# main.net
KiCad netlist of a schematic drawn in Altium Designer
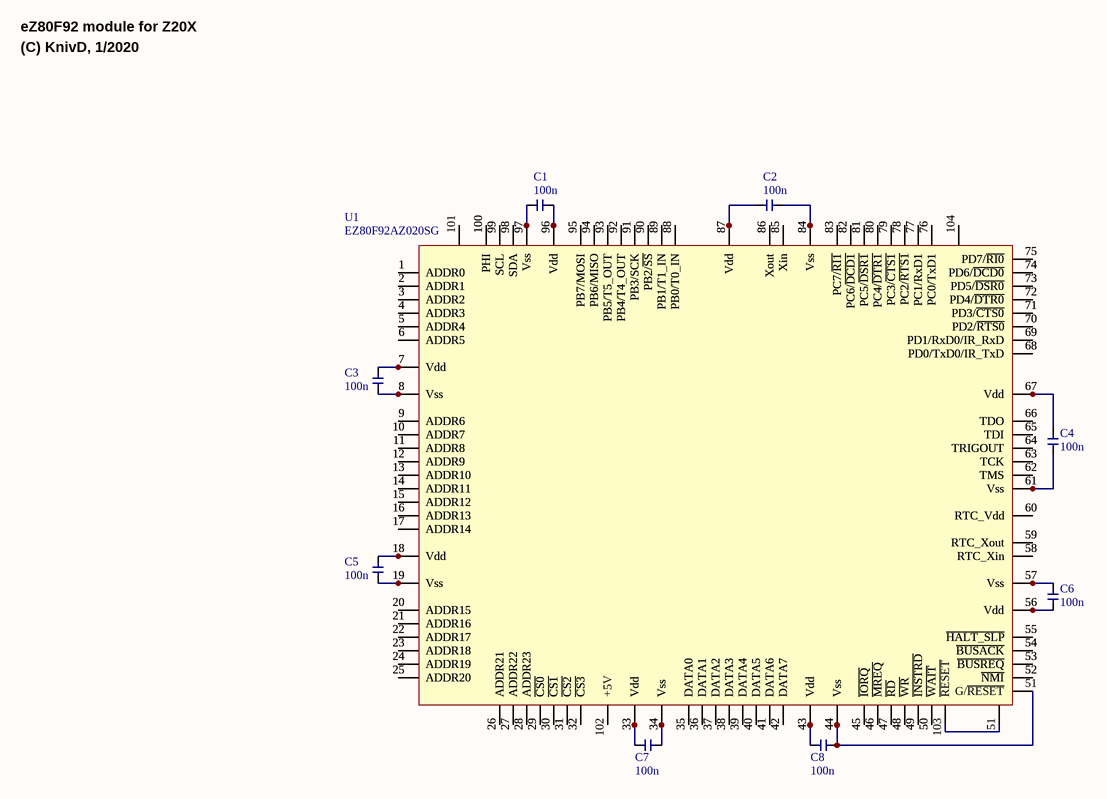
[diagram p0: main.SchDoc]

(export (version "E")
  (design (tool "Eeschema 10.0.6"))
  (components
    (comp (ref "C1")
      (value "100n")
      (footprint "_0805_CAP")
      (description "Capacitor")
      (libsource (lib "Discretes") (part "Capacitor"))
    )
    (comp (ref "C2")
      (value "100n")
      (footprint "_0805_CAP")
      (description "Capacitor")
      (libsource (lib "Discretes") (part "Capacitor"))
    )
    (comp (ref "C3")
      (value "100n")
      (footprint "_0805_CAP")
      (description "Capacitor")
      (libsource (lib "Discretes") (part "Capacitor"))
    )
    (comp (ref "C4")
      (value "100n")
      (footprint "_0805_CAP")
      (description "Capacitor")
      (libsource (lib "Discretes") (part "Capacitor"))
    )
    (comp (ref "C5")
      (value "100n")
      (footprint "_0805_CAP")
      (description "Capacitor")
      (libsource (lib "Discretes") (part "Capacitor"))
    )
    (comp (ref "C6")
      (value "100n")
      (footprint "_0805_CAP")
      (description "Capacitor")
      (libsource (lib "Discretes") (part "Capacitor"))
    )
    (comp (ref "C7")
      (value "100n")
      (footprint "_0805_CAP")
      (description "Capacitor")
      (libsource (lib "Discretes") (part "Capacitor"))
    )
    (comp (ref "C8")
      (value "100n")
      (footprint "_0805_CAP")
      (description "Capacitor")
      (libsource (lib "Discretes") (part "Capacitor"))
    )
    (comp (ref "MOD1")
      (value "Z20X CPU Module")
      (footprint "PGA100X15")
      (libsource (lib "Modules") (part "Z20X CPU Module"))
    )
    (comp (ref "U1")
      (value "EZ80F92AZ020SG")
      (footprint "QFP50P1600X1600X170-100N")
      (description "eZ80Acclaim!® Flash Microcontrollers")
      (fields (field (name "MANUFACTURER") "Zilog"))
      (libsource (lib "IC Microcontrollers and Processors") (part "eZ80F92/93"))
    )
  )
  (nets
    (net (code "1") (name "Net-(C1-Pad1)") (class "Default")
      (node (ref "C1") (pin "1") (pintype "passive"))
      (node (ref "MOD1") (pin "96") (pinfunction "Vdd_96") (pintype "passive"))
      (node (ref "U1") (pin "96") (pinfunction "Vdd_96") (pintype "passive"))
    )
    (net (code "2") (name "Net-(C1-Pad2)") (class "Default")
      (node (ref "C1") (pin "2") (pintype "passive"))
      (node (ref "MOD1") (pin "97") (pinfunction "Vss_97") (pintype "passive"))
      (node (ref "U1") (pin "97") (pinfunction "Vss_97") (pintype "passive"))
    )
    (net (code "3") (name "Net-(C2-Pad1)") (class "Default")
      (node (ref "C2") (pin "1") (pintype "passive"))
      (node (ref "MOD1") (pin "84") (pinfunction "Vss_84") (pintype "passive"))
      (node (ref "U1") (pin "84") (pinfunction "Vss_84") (pintype "passive"))
    )
    (net (code "4") (name "Net-(C2-Pad2)") (class "Default")
      (node (ref "C2") (pin "2") (pintype "passive"))
      (node (ref "MOD1") (pin "87") (pinfunction "Vdd_87") (pintype "passive"))
      (node (ref "U1") (pin "87") (pinfunction "Vdd_87") (pintype "passive"))
    )
    (net (code "5") (name "Net-(C3-Pad1)") (class "Default")
      (node (ref "C3") (pin "1") (pintype "passive"))
      (node (ref "MOD1") (pin "7") (pinfunction "Vdd_7") (pintype "passive"))
      (node (ref "U1") (pin "7") (pinfunction "Vdd_7") (pintype "passive"))
    )
    (net (code "6") (name "Net-(C3-Pad2)") (class "Default")
      (node (ref "C3") (pin "2") (pintype "passive"))
      (node (ref "MOD1") (pin "8") (pinfunction "Vss_8") (pintype "passive"))
      (node (ref "U1") (pin "8") (pinfunction "Vss_8") (pintype "passive"))
    )
    (net (code "7") (name "Net-(C4-Pad1)") (class "Default")
      (node (ref "C4") (pin "1") (pintype "passive"))
      (node (ref "MOD1") (pin "61") (pinfunction "Vss_61") (pintype "passive"))
      (node (ref "U1") (pin "61") (pinfunction "Vss_61") (pintype "passive"))
    )
    (net (code "8") (name "Net-(C4-Pad2)") (class "Default")
      (node (ref "C4") (pin "2") (pintype "passive"))
      (node (ref "MOD1") (pin "67") (pinfunction "Vdd_67") (pintype "passive"))
      (node (ref "U1") (pin "67") (pinfunction "Vdd_67") (pintype "passive"))
    )
    (net (code "9") (name "Net-(C5-Pad1)") (class "Default")
      (node (ref "C5") (pin "1") (pintype "passive"))
      (node (ref "MOD1") (pin "18") (pinfunction "Vdd_18") (pintype "passive"))
      (node (ref "U1") (pin "18") (pinfunction "Vdd_18") (pintype "passive"))
    )
    (net (code "10") (name "Net-(C5-Pad2)") (class "Default")
      (node (ref "C5") (pin "2") (pintype "passive"))
      (node (ref "MOD1") (pin "19") (pinfunction "Vss_19") (pintype "passive"))
      (node (ref "U1") (pin "19") (pinfunction "Vss_19") (pintype "passive"))
    )
    (net (code "11") (name "Net-(C6-Pad1)") (class "Default")
      (node (ref "C6") (pin "1") (pintype "passive"))
      (node (ref "MOD1") (pin "56") (pinfunction "Vdd_56") (pintype "passive"))
      (node (ref "U1") (pin "56") (pinfunction "Vdd_56") (pintype "passive"))
    )
    (net (code "12") (name "Net-(C6-Pad2)") (class "Default")
      (node (ref "C6") (pin "2") (pintype "passive"))
      (node (ref "MOD1") (pin "57") (pinfunction "Vss_57") (pintype "passive"))
      (node (ref "U1") (pin "57") (pinfunction "Vss_57") (pintype "passive"))
    )
    (net (code "13") (name "Net-(C7-Pad1)") (class "Default")
      (node (ref "C7") (pin "1") (pintype "passive"))
      (node (ref "MOD1") (pin "33") (pinfunction "Vdd_33") (pintype "passive"))
      (node (ref "U1") (pin "33") (pinfunction "Vdd_33") (pintype "passive"))
    )
    (net (code "14") (name "Net-(C7-Pad2)") (class "Default")
      (node (ref "C7") (pin "2") (pintype "passive"))
      (node (ref "MOD1") (pin "34") (pinfunction "Vss_34") (pintype "passive"))
      (node (ref "U1") (pin "34") (pinfunction "Vss_34") (pintype "passive"))
    )
    (net (code "15") (name "Net-(C8-Pad1)") (class "Default")
      (node (ref "C8") (pin "1") (pintype "passive"))
      (node (ref "MOD1") (pin "43") (pinfunction "Vdd_43") (pintype "passive"))
      (node (ref "U1") (pin "43") (pinfunction "Vdd_43") (pintype "passive"))
    )
    (net (code "16") (name "Net-(MOD1-ADDR0)") (class "Default")
      (node (ref "MOD1") (pin "1") (pinfunction "ADDR0_1") (pintype "passive"))
      (node (ref "U1") (pin "1") (pinfunction "ADDR0_1") (pintype "passive"))
    )
    (net (code "17") (name "Net-(MOD1-ADDR1)") (class "Default")
      (node (ref "MOD1") (pin "2") (pinfunction "ADDR1_2") (pintype "passive"))
      (node (ref "U1") (pin "2") (pinfunction "ADDR1_2") (pintype "passive"))
    )
    (net (code "18") (name "Net-(MOD1-ADDR2)") (class "Default")
      (node (ref "MOD1") (pin "3") (pinfunction "ADDR2_3") (pintype "passive"))
      (node (ref "U1") (pin "3") (pinfunction "ADDR2_3") (pintype "passive"))
    )
    (net (code "19") (name "Net-(MOD1-ADDR3)") (class "Default")
      (node (ref "MOD1") (pin "4") (pinfunction "ADDR3_4") (pintype "passive"))
      (node (ref "U1") (pin "4") (pinfunction "ADDR3_4") (pintype "passive"))
    )
    (net (code "20") (name "Net-(MOD1-ADDR4)") (class "Default")
      (node (ref "MOD1") (pin "5") (pinfunction "ADDR4_5") (pintype "passive"))
      (node (ref "U1") (pin "5") (pinfunction "ADDR4_5") (pintype "passive"))
    )
    (net (code "21") (name "Net-(MOD1-ADDR5)") (class "Default")
      (node (ref "MOD1") (pin "6") (pinfunction "ADDR5_6") (pintype "passive"))
      (node (ref "U1") (pin "6") (pinfunction "ADDR5_6") (pintype "passive"))
    )
    (net (code "22") (name "Net-(MOD1-ADDR6)") (class "Default")
      (node (ref "MOD1") (pin "9") (pinfunction "ADDR6_9") (pintype "passive"))
      (node (ref "U1") (pin "9") (pinfunction "ADDR6_9") (pintype "passive"))
    )
    (net (code "23") (name "Net-(MOD1-ADDR7)") (class "Default")
      (node (ref "MOD1") (pin "10") (pinfunction "ADDR7_10") (pintype "passive"))
      (node (ref "U1") (pin "10") (pinfunction "ADDR7_10") (pintype "passive"))
    )
    (net (code "24") (name "Net-(MOD1-ADDR8)") (class "Default")
      (node (ref "MOD1") (pin "11") (pinfunction "ADDR8_11") (pintype "passive"))
      (node (ref "U1") (pin "11") (pinfunction "ADDR8_11") (pintype "passive"))
    )
    (net (code "25") (name "Net-(MOD1-ADDR9)") (class "Default")
      (node (ref "MOD1") (pin "12") (pinfunction "ADDR9_12") (pintype "passive"))
      (node (ref "U1") (pin "12") (pinfunction "ADDR9_12") (pintype "passive"))
    )
    (net (code "26") (name "Net-(MOD1-ADDR10)") (class "Default")
      (node (ref "MOD1") (pin "13") (pinfunction "ADDR10_13") (pintype "passive"))
      (node (ref "U1") (pin "13") (pinfunction "ADDR10_13") (pintype "passive"))
    )
    (net (code "27") (name "Net-(MOD1-ADDR11)") (class "Default")
      (node (ref "MOD1") (pin "14") (pinfunction "ADDR11_14") (pintype "passive"))
      (node (ref "U1") (pin "14") (pinfunction "ADDR11_14") (pintype "passive"))
    )
    (net (code "28") (name "Net-(MOD1-ADDR12)") (class "Default")
      (node (ref "MOD1") (pin "15") (pinfunction "ADDR12_15") (pintype "passive"))
      (node (ref "U1") (pin "15") (pinfunction "ADDR12_15") (pintype "passive"))
    )
    (net (code "29") (name "Net-(MOD1-ADDR13)") (class "Default")
      (node (ref "MOD1") (pin "16") (pinfunction "ADDR13_16") (pintype "passive"))
      (node (ref "U1") (pin "16") (pinfunction "ADDR13_16") (pintype "passive"))
    )
    (net (code "30") (name "Net-(MOD1-ADDR14)") (class "Default")
      (node (ref "MOD1") (pin "17") (pinfunction "ADDR14_17") (pintype "passive"))
      (node (ref "U1") (pin "17") (pinfunction "ADDR14_17") (pintype "passive"))
    )
    (net (code "31") (name "Net-(MOD1-ADDR15)") (class "Default")
      (node (ref "MOD1") (pin "20") (pinfunction "ADDR15_20") (pintype "passive"))
      (node (ref "U1") (pin "20") (pinfunction "ADDR15_20") (pintype "passive"))
    )
    (net (code "32") (name "Net-(MOD1-ADDR16)") (class "Default")
      (node (ref "MOD1") (pin "21") (pinfunction "ADDR16_21") (pintype "passive"))
      (node (ref "U1") (pin "21") (pinfunction "ADDR16_21") (pintype "passive"))
    )
    (net (code "33") (name "Net-(MOD1-ADDR17)") (class "Default")
      (node (ref "MOD1") (pin "22") (pinfunction "ADDR17_22") (pintype "passive"))
      (node (ref "U1") (pin "22") (pinfunction "ADDR17_22") (pintype "passive"))
    )
    (net (code "34") (name "Net-(MOD1-ADDR18)") (class "Default")
      (node (ref "MOD1") (pin "23") (pinfunction "ADDR18_23") (pintype "passive"))
      (node (ref "U1") (pin "23") (pinfunction "ADDR18_23") (pintype "passive"))
    )
    (net (code "35") (name "Net-(MOD1-ADDR19)") (class "Default")
      (node (ref "MOD1") (pin "24") (pinfunction "ADDR19_24") (pintype "passive"))
      (node (ref "U1") (pin "24") (pinfunction "ADDR19_24") (pintype "passive"))
    )
    (net (code "36") (name "Net-(MOD1-ADDR20)") (class "Default")
      (node (ref "MOD1") (pin "25") (pinfunction "ADDR20_25") (pintype "passive"))
      (node (ref "U1") (pin "25") (pinfunction "ADDR20_25") (pintype "passive"))
    )
    (net (code "37") (name "Net-(MOD1-ADDR21)") (class "Default")
      (node (ref "MOD1") (pin "26") (pinfunction "ADDR21_26") (pintype "passive"))
      (node (ref "U1") (pin "26") (pinfunction "ADDR21_26") (pintype "passive"))
    )
    (net (code "38") (name "Net-(MOD1-ADDR22)") (class "Default")
      (node (ref "MOD1") (pin "27") (pinfunction "ADDR22_27") (pintype "passive"))
      (node (ref "U1") (pin "27") (pinfunction "ADDR22_27") (pintype "passive"))
    )
    (net (code "39") (name "Net-(MOD1-ADDR23)") (class "Default")
      (node (ref "MOD1") (pin "28") (pinfunction "ADDR23_28") (pintype "passive"))
      (node (ref "U1") (pin "28") (pinfunction "ADDR23_28") (pintype "passive"))
    )
    (net (code "40") (name "Net-(MOD1-DATA0)") (class "Default")
      (node (ref "MOD1") (pin "35") (pinfunction "DATA0_35") (pintype "passive"))
      (node (ref "U1") (pin "35") (pinfunction "DATA0_35") (pintype "passive"))
    )
    (net (code "41") (name "Net-(MOD1-DATA1)") (class "Default")
      (node (ref "MOD1") (pin "36") (pinfunction "DATA1_36") (pintype "passive"))
      (node (ref "U1") (pin "36") (pinfunction "DATA1_36") (pintype "passive"))
    )
    (net (code "42") (name "Net-(MOD1-DATA2)") (class "Default")
      (node (ref "MOD1") (pin "37") (pinfunction "DATA2_37") (pintype "passive"))
      (node (ref "U1") (pin "37") (pinfunction "DATA2_37") (pintype "passive"))
    )
    (net (code "43") (name "Net-(MOD1-DATA3)") (class "Default")
      (node (ref "MOD1") (pin "38") (pinfunction "DATA3_38") (pintype "passive"))
      (node (ref "U1") (pin "38") (pinfunction "DATA3_38") (pintype "passive"))
    )
    (net (code "44") (name "Net-(MOD1-DATA4)") (class "Default")
      (node (ref "MOD1") (pin "39") (pinfunction "DATA4_39") (pintype "passive"))
      (node (ref "U1") (pin "39") (pinfunction "DATA4_39") (pintype "passive"))
    )
    (net (code "45") (name "Net-(MOD1-DATA5)") (class "Default")
      (node (ref "MOD1") (pin "40") (pinfunction "DATA5_40") (pintype "passive"))
      (node (ref "U1") (pin "40") (pinfunction "DATA5_40") (pintype "passive"))
    )
    (net (code "46") (name "Net-(MOD1-DATA6)") (class "Default")
      (node (ref "MOD1") (pin "41") (pinfunction "DATA6_41") (pintype "passive"))
      (node (ref "U1") (pin "41") (pinfunction "DATA6_41") (pintype "passive"))
    )
    (net (code "47") (name "Net-(MOD1-DATA7)") (class "Default")
      (node (ref "MOD1") (pin "42") (pinfunction "DATA7_42") (pintype "passive"))
      (node (ref "U1") (pin "42") (pinfunction "DATA7_42") (pintype "passive"))
    )
    (net (code "48") (name "Net-(MOD1-G{slash}~{RESET})") (class "Default")
      (node (ref "C8") (pin "2") (pintype "passive"))
      (node (ref "MOD1") (pin "44") (pinfunction "Vss_44") (pintype "passive"))
      (node (ref "MOD1") (pin "51") (pinfunction "G/~{RESET}_51") (pintype "passive"))
      (node (ref "U1") (pin "44") (pinfunction "Vss_44") (pintype "passive"))
    )
    (net (code "49") (name "Net-(MOD1-PB0{slash}T0_IN)") (class "Default")
      (node (ref "MOD1") (pin "88") (pinfunction "PB0/T0_IN_88") (pintype "passive"))
      (node (ref "U1") (pin "88") (pinfunction "PB0/T0_IN_88") (pintype "passive"))
    )
    (net (code "50") (name "Net-(MOD1-PB1{slash}T1_IN)") (class "Default")
      (node (ref "MOD1") (pin "89") (pinfunction "PB1/T1_IN_89") (pintype "passive"))
      (node (ref "U1") (pin "89") (pinfunction "PB1/T1_IN_89") (pintype "passive"))
    )
    (net (code "51") (name "Net-(MOD1-PB2{slash}~{SS})") (class "Default")
      (node (ref "MOD1") (pin "90") (pinfunction "PB2/~{SS}_90") (pintype "passive"))
      (node (ref "U1") (pin "90") (pinfunction "PB2/~{SS}_90") (pintype "passive"))
    )
    (net (code "52") (name "Net-(MOD1-PB3{slash}SCK)") (class "Default")
      (node (ref "MOD1") (pin "91") (pinfunction "PB3/SCK_91") (pintype "passive"))
      (node (ref "U1") (pin "91") (pinfunction "PB3/SCK_91") (pintype "passive"))
    )
    (net (code "53") (name "Net-(MOD1-PB4{slash}T4_OUT)") (class "Default")
      (node (ref "MOD1") (pin "92") (pinfunction "PB4/T4_OUT_92") (pintype "passive"))
      (node (ref "U1") (pin "92") (pinfunction "PB4/T4_OUT_92") (pintype "passive"))
    )
    (net (code "54") (name "Net-(MOD1-PB5{slash}T5_OUT)") (class "Default")
      (node (ref "MOD1") (pin "93") (pinfunction "PB5/T5_OUT_93") (pintype "passive"))
      (node (ref "U1") (pin "93") (pinfunction "PB5/T5_OUT_93") (pintype "passive"))
    )
    (net (code "55") (name "Net-(MOD1-PB6{slash}MISO)") (class "Default")
      (node (ref "MOD1") (pin "94") (pinfunction "PB6/MISO_94") (pintype "passive"))
      (node (ref "U1") (pin "94") (pinfunction "PB6/MISO_94") (pintype "passive"))
    )
    (net (code "56") (name "Net-(MOD1-PB7{slash}MOSI)") (class "Default")
      (node (ref "MOD1") (pin "95") (pinfunction "PB7/MOSI_95") (pintype "passive"))
      (node (ref "U1") (pin "95") (pinfunction "PB7/MOSI_95") (pintype "passive"))
    )
    (net (code "57") (name "Net-(MOD1-PC0{slash}TxD1)") (class "Default")
      (node (ref "MOD1") (pin "76") (pinfunction "PC0/TxD1_76") (pintype "passive"))
      (node (ref "U1") (pin "76") (pinfunction "PC0/TxD1_76") (pintype "passive"))
    )
    (net (code "58") (name "Net-(MOD1-PC1{slash}RxD1)") (class "Default")
      (node (ref "MOD1") (pin "77") (pinfunction "PC1/RxD1_77") (pintype "passive"))
      (node (ref "U1") (pin "77") (pinfunction "PC1/RxD1_77") (pintype "passive"))
    )
    (net (code "59") (name "Net-(MOD1-PC2{slash}~{RTS1})") (class "Default")
      (node (ref "MOD1") (pin "78") (pinfunction "PC2/~{RTS1}_78") (pintype "passive"))
      (node (ref "U1") (pin "78") (pinfunction "PC2/~{RTS1}_78") (pintype "passive"))
    )
    (net (code "60") (name "Net-(MOD1-PC3{slash}~{CTS1})") (class "Default")
      (node (ref "MOD1") (pin "79") (pinfunction "PC3/~{CTS1}_79") (pintype "passive"))
      (node (ref "U1") (pin "79") (pinfunction "PC3/~{CTS1}_79") (pintype "passive"))
    )
    (net (code "61") (name "Net-(MOD1-PC4{slash}~{DTR1})") (class "Default")
      (node (ref "MOD1") (pin "80") (pinfunction "PC4/~{DTR1}_80") (pintype "passive"))
      (node (ref "U1") (pin "80") (pinfunction "PC4/~{DTR1}_80") (pintype "passive"))
    )
    (net (code "62") (name "Net-(MOD1-PC5{slash}~{DSR1})") (class "Default")
      (node (ref "MOD1") (pin "81") (pinfunction "PC5/~{DSR1}_81") (pintype "passive"))
      (node (ref "U1") (pin "81") (pinfunction "PC5/~{DSR1}_81") (pintype "passive"))
    )
    (net (code "63") (name "Net-(MOD1-PC6{slash}~{DCD1})") (class "Default")
      (node (ref "MOD1") (pin "82") (pinfunction "PC6/~{DCD1}_82") (pintype "passive"))
      (node (ref "U1") (pin "82") (pinfunction "PC6/~{DCD1}_82") (pintype "passive"))
    )
    (net (code "64") (name "Net-(MOD1-PC7{slash}~{RI1})") (class "Default")
      (node (ref "MOD1") (pin "83") (pinfunction "PC7/~{RI1}_83") (pintype "passive"))
      (node (ref "U1") (pin "83") (pinfunction "PC7/~{RI1}_83") (pintype "passive"))
    )
    (net (code "65") (name "Net-(MOD1-PD0{slash}TxD0{slash}IR_TxD)") (class "Default")
      (node (ref "MOD1") (pin "68") (pinfunction "PD0/TxD0/IR_TxD_68") (pintype "passive"))
      (node (ref "U1") (pin "68") (pinfunction "PD0/TxD0/IR_TxD_68") (pintype "passive"))
    )
    (net (code "66") (name "Net-(MOD1-PD1{slash}RxD0{slash}IR_RxD)") (class "Default")
      (node (ref "MOD1") (pin "69") (pinfunction "PD1/RxD0/IR_RxD_69") (pintype "passive"))
      (node (ref "U1") (pin "69") (pinfunction "PD1/RxD0/IR_RxD_69") (pintype "passive"))
    )
    (net (code "67") (name "Net-(MOD1-PD2{slash}~{RTS0})") (class "Default")
      (node (ref "MOD1") (pin "70") (pinfunction "PD2/~{RTS0}_70") (pintype "passive"))
      (node (ref "U1") (pin "70") (pinfunction "PD2/~{RTS0}_70") (pintype "passive"))
    )
    (net (code "68") (name "Net-(MOD1-PD3{slash}~{CTS0})") (class "Default")
      (node (ref "MOD1") (pin "71") (pinfunction "PD3/~{CTS0}_71") (pintype "passive"))
      (node (ref "U1") (pin "71") (pinfunction "PD3/~{CTS0}_71") (pintype "passive"))
    )
    (net (code "69") (name "Net-(MOD1-PD4{slash}~{DTR0})") (class "Default")
      (node (ref "MOD1") (pin "72") (pinfunction "PD4/~{DTR0}_72") (pintype "passive"))
      (node (ref "U1") (pin "72") (pinfunction "PD4/~{DTR0}_72") (pintype "passive"))
    )
    (net (code "70") (name "Net-(MOD1-PD5{slash}~{DSR0})") (class "Default")
      (node (ref "MOD1") (pin "73") (pinfunction "PD5/~{DSR0}_73") (pintype "passive"))
      (node (ref "U1") (pin "73") (pinfunction "PD5/~{DSR0}_73") (pintype "passive"))
    )
    (net (code "71") (name "Net-(MOD1-PD6{slash}~{DCD0})") (class "Default")
      (node (ref "MOD1") (pin "74") (pinfunction "PD6/~{DCD0}_74") (pintype "passive"))
      (node (ref "U1") (pin "74") (pinfunction "PD6/~{DCD0}_74") (pintype "passive"))
    )
    (net (code "72") (name "Net-(MOD1-PD7{slash}~{RI0})") (class "Default")
      (node (ref "MOD1") (pin "75") (pinfunction "PD7/~{RI0}_75") (pintype "passive"))
      (node (ref "U1") (pin "75") (pinfunction "PD7/~{RI0}_75") (pintype "passive"))
    )
    (net (code "73") (name "Net-(MOD1-PHI)") (class "Default")
      (node (ref "MOD1") (pin "100") (pinfunction "PHI_100") (pintype "passive"))
      (node (ref "U1") (pin "100") (pinfunction "PHI_100") (pintype "passive"))
    )
    (net (code "74") (name "Net-(MOD1-RTC_Vdd)") (class "Default")
      (node (ref "MOD1") (pin "60") (pinfunction "RTC_Vdd_60") (pintype "passive"))
      (node (ref "U1") (pin "60") (pinfunction "RTC_Vdd_60") (pintype "passive"))
    )
    (net (code "75") (name "Net-(MOD1-RTC_Xin)") (class "Default")
      (node (ref "MOD1") (pin "58") (pinfunction "RTC_Xin_58") (pintype "passive"))
      (node (ref "U1") (pin "58") (pinfunction "RTC_Xin_58") (pintype "passive"))
    )
    (net (code "76") (name "Net-(MOD1-RTC_Xout)") (class "Default")
      (node (ref "MOD1") (pin "59") (pinfunction "RTC_Xout_59") (pintype "passive"))
      (node (ref "U1") (pin "59") (pinfunction "RTC_Xout_59") (pintype "passive"))
    )
    (net (code "77") (name "Net-(MOD1-SCL)") (class "Default")
      (node (ref "MOD1") (pin "99") (pinfunction "SCL_99") (pintype "passive"))
      (node (ref "U1") (pin "99") (pinfunction "SCL_99") (pintype "passive"))
    )
    (net (code "78") (name "Net-(MOD1-SDA)") (class "Default")
      (node (ref "MOD1") (pin "98") (pinfunction "SDA_98") (pintype "passive"))
      (node (ref "U1") (pin "98") (pinfunction "SDA_98") (pintype "passive"))
    )
    (net (code "79") (name "Net-(MOD1-TCK)") (class "Default")
      (node (ref "MOD1") (pin "63") (pinfunction "TCK_63") (pintype "passive"))
      (node (ref "U1") (pin "63") (pinfunction "TCK_63") (pintype "passive"))
    )
    (net (code "80") (name "Net-(MOD1-TDI)") (class "Default")
      (node (ref "MOD1") (pin "65") (pinfunction "TDI_65") (pintype "passive"))
      (node (ref "U1") (pin "65") (pinfunction "TDI_65") (pintype "passive"))
    )
    (net (code "81") (name "Net-(MOD1-TDO)") (class "Default")
      (node (ref "MOD1") (pin "66") (pinfunction "TDO_66") (pintype "passive"))
      (node (ref "U1") (pin "66") (pinfunction "TDO_66") (pintype "passive"))
    )
    (net (code "82") (name "Net-(MOD1-TMS)") (class "Default")
      (node (ref "MOD1") (pin "62") (pinfunction "TMS_62") (pintype "passive"))
      (node (ref "U1") (pin "62") (pinfunction "TMS_62") (pintype "passive"))
    )
    (net (code "83") (name "Net-(MOD1-TRIGOUT)") (class "Default")
      (node (ref "MOD1") (pin "64") (pinfunction "TRIGOUT_64") (pintype "passive"))
      (node (ref "U1") (pin "64") (pinfunction "TRIGOUT_64") (pintype "passive"))
    )
    (net (code "84") (name "Net-(MOD1-Xin)") (class "Default")
      (node (ref "MOD1") (pin "85") (pinfunction "Xin_85") (pintype "passive"))
      (node (ref "U1") (pin "85") (pinfunction "Xin_85") (pintype "passive"))
    )
    (net (code "85") (name "Net-(MOD1-Xout)") (class "Default")
      (node (ref "MOD1") (pin "86") (pinfunction "Xout_86") (pintype "passive"))
      (node (ref "U1") (pin "86") (pinfunction "Xout_86") (pintype "passive"))
    )
    (net (code "86") (name "Net-(MOD1-~{BUSACK})") (class "Default")
      (node (ref "MOD1") (pin "54") (pinfunction "~{BUSACK}_54") (pintype "passive"))
      (node (ref "U1") (pin "54") (pinfunction "~{BUSACK}_54") (pintype "passive"))
    )
    (net (code "87") (name "Net-(MOD1-~{BUSREQ})") (class "Default")
      (node (ref "MOD1") (pin "53") (pinfunction "~{BUSREQ}_53") (pintype "passive"))
      (node (ref "U1") (pin "53") (pinfunction "~{BUSREQ}_53") (pintype "passive"))
    )
    (net (code "88") (name "Net-(MOD1-~{CS0})") (class "Default")
      (node (ref "MOD1") (pin "29") (pinfunction "~{CS0}_29") (pintype "passive"))
      (node (ref "U1") (pin "29") (pinfunction "~{CS0}_29") (pintype "passive"))
    )
    (net (code "89") (name "Net-(MOD1-~{CS1})") (class "Default")
      (node (ref "MOD1") (pin "30") (pinfunction "~{CS1}_30") (pintype "passive"))
      (node (ref "U1") (pin "30") (pinfunction "~{CS1}_30") (pintype "passive"))
    )
    (net (code "90") (name "Net-(MOD1-~{CS2})") (class "Default")
      (node (ref "MOD1") (pin "31") (pinfunction "~{CS2}_31") (pintype "passive"))
      (node (ref "U1") (pin "31") (pinfunction "~{CS2}_31") (pintype "passive"))
    )
    (net (code "91") (name "Net-(MOD1-~{CS3})") (class "Default")
      (node (ref "MOD1") (pin "32") (pinfunction "~{CS3}_32") (pintype "passive"))
      (node (ref "U1") (pin "32") (pinfunction "~{CS3}_32") (pintype "passive"))
    )
    (net (code "92") (name "Net-(MOD1-~{HALT_SLP})") (class "Default")
      (node (ref "MOD1") (pin "55") (pinfunction "~{HALT_SLP}_55") (pintype "passive"))
      (node (ref "U1") (pin "55") (pinfunction "~{HALT_SLP}_55") (pintype "passive"))
    )
    (net (code "93") (name "Net-(MOD1-~{INSTRD})") (class "Default")
      (node (ref "MOD1") (pin "49") (pinfunction "~{INSTRD}_49") (pintype "passive"))
      (node (ref "U1") (pin "49") (pinfunction "~{INSTRD}_49") (pintype "passive"))
    )
    (net (code "94") (name "Net-(MOD1-~{IORQ})") (class "Default")
      (node (ref "MOD1") (pin "45") (pinfunction "~{IORQ}_45") (pintype "passive"))
      (node (ref "U1") (pin "45") (pinfunction "~{IORQ}_45") (pintype "passive"))
    )
    (net (code "95") (name "Net-(MOD1-~{MREQ})") (class "Default")
      (node (ref "MOD1") (pin "46") (pinfunction "~{MREQ}_46") (pintype "passive"))
      (node (ref "U1") (pin "46") (pinfunction "~{MREQ}_46") (pintype "passive"))
    )
    (net (code "96") (name "Net-(MOD1-~{NMI})") (class "Default")
      (node (ref "MOD1") (pin "52") (pinfunction "~{NMI}_52") (pintype "passive"))
      (node (ref "U1") (pin "52") (pinfunction "~{NMI}_52") (pintype "passive"))
    )
    (net (code "97") (name "Net-(MOD1-~{RD})") (class "Default")
      (node (ref "MOD1") (pin "47") (pinfunction "~{RD}_47") (pintype "passive"))
      (node (ref "U1") (pin "47") (pinfunction "~{RD}_47") (pintype "passive"))
    )
    (net (code "98") (name "Net-(MOD1-~{RESET})") (class "Default")
      (node (ref "MOD1") (pin "103") (pinfunction "~{RESET}_103") (pintype "passive"))
      (node (ref "U1") (pin "51") (pinfunction "~{RESET}_51") (pintype "passive"))
    )
    (net (code "99") (name "Net-(MOD1-~{WAIT})") (class "Default")
      (node (ref "MOD1") (pin "50") (pinfunction "~{WAIT}_50") (pintype "passive"))
      (node (ref "U1") (pin "50") (pinfunction "~{WAIT}_50") (pintype "passive"))
    )
    (net (code "100") (name "Net-(MOD1-~{WR})") (class "Default")
      (node (ref "MOD1") (pin "48") (pinfunction "~{WR}_48") (pintype "passive"))
      (node (ref "U1") (pin "48") (pinfunction "~{WR}_48") (pintype "passive"))
    )
    (net (code "101") (name "unconnected-(MOD1-+5V-Pad102)") (class "Default")
      (node (ref "MOD1") (pin "102") (pinfunction "+5V_102") (pintype "passive"))
    )
    (net (code "102") (name "unconnected-(MOD1-Pad101)") (class "Default")
      (node (ref "MOD1") (pin "101") (pintype "passive"))
    )
    (net (code "103") (name "unconnected-(MOD1-Pad104)") (class "Default")
      (node (ref "MOD1") (pin "104") (pintype "passive"))
    )
  )
)
